# design.net
KiCad netlist of a schematic drawn in Altium Designer
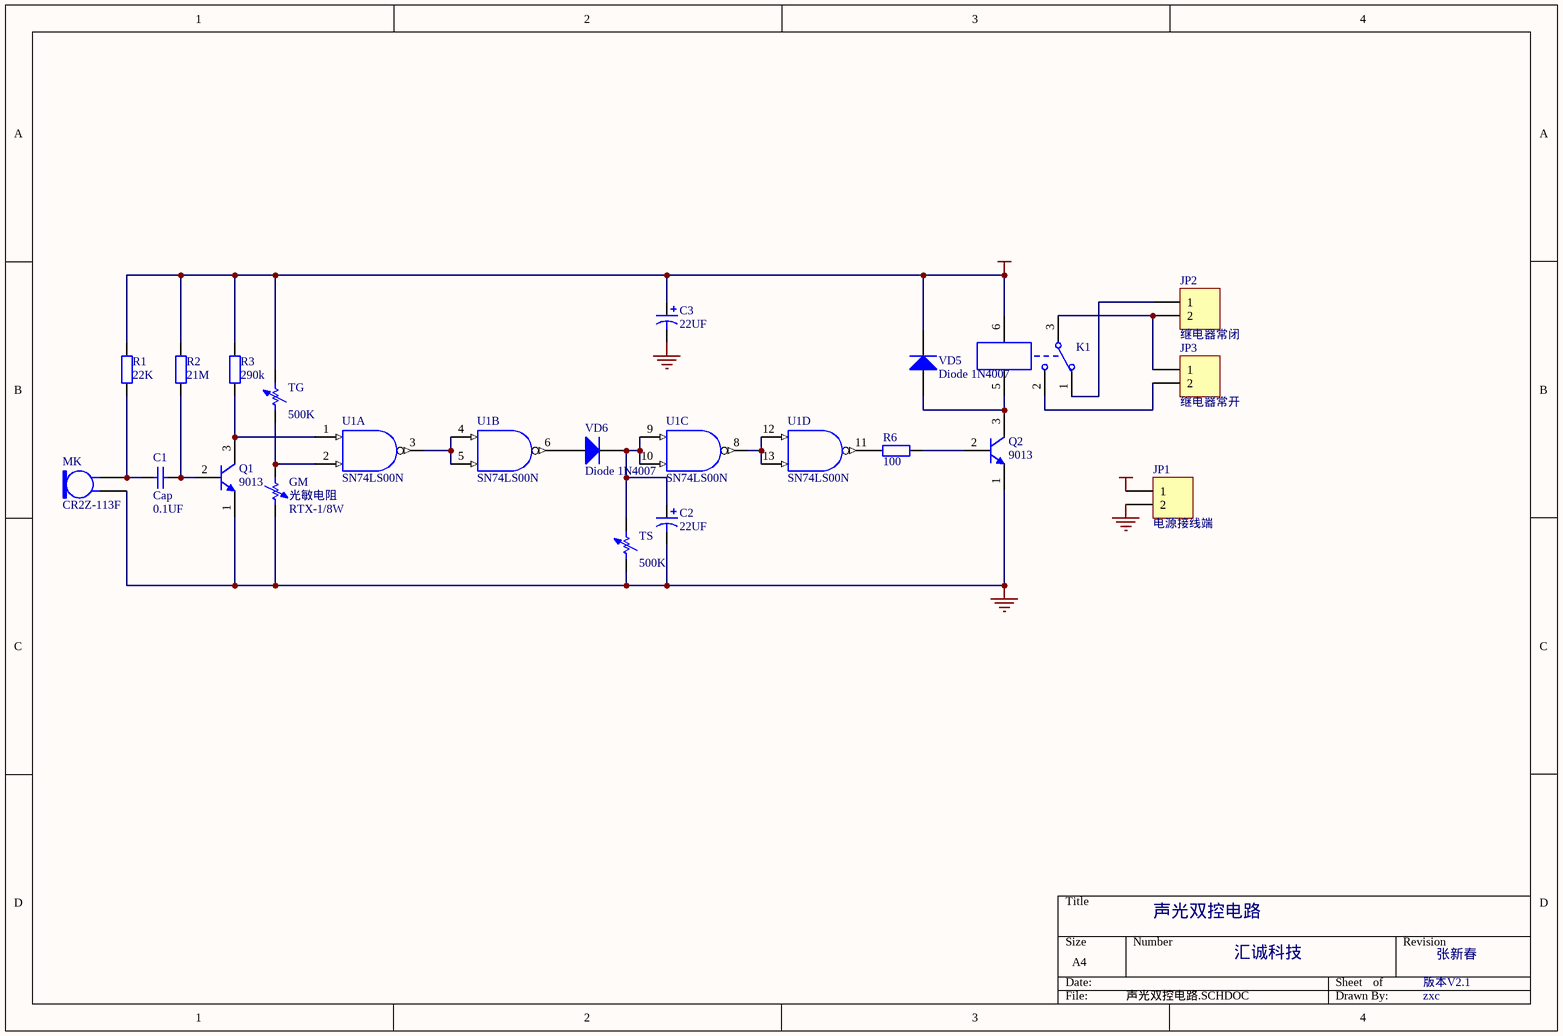
[diagram p0: 声光双控电路.SCHDOC]

(export (version "E")
  (design (tool "Eeschema 10.0.6"))
  (components
    (comp (ref "C1")
      (value "Cap")
      (footprint "HDR-2")
      (description "Capacitor")
      (fields (field (name "ALTIUM_VALUE") "0.1UF") (field (name "PUBLISHER") "Altium Limited"))
      (libsource (lib "Miscellaneous Devices") (part "Cap"))
    )
    (comp (ref "C2")
      (value "22UF")
      (footprint "C-DJ-4")
      (description "Polarized Capacitor (Radial)")
      (fields (field (name "PUBLISHER") "Altium Limited"))
      (libsource (lib "Miscellaneous Devices") (part "Cap Pol1"))
    )
    (comp (ref "C3")
      (value "22UF")
      (footprint "C-DJ-4")
      (description "Polarized Capacitor (Radial)")
      (fields (field (name "PUBLISHER") "Altium Limited"))
      (libsource (lib "Miscellaneous Devices") (part "Cap Pol1"))
    )
    (comp (ref "GM")
      (value "光敏电阻")
      (footprint "HDR-2")
      (description "Variable Resistor")
      (fields (field (name "ALTIUM_VALUE") "RTX-1/8W") (field (name "PUBLISHER") "Altium Limited"))
      (libsource (lib "Miscellaneous Devices") (part "Res Adj1"))
    )
    (comp (ref "JP1")
      (value "电源接线端")
      (footprint "JK128")
      (description "Header, 2-Pin, Right Angle")
      (fields (field (name "PUBLISHER") "Altium Limited"))
      (libsource (lib "Miscellaneous Connectors") (part "Header 2H"))
    )
    (comp (ref "JP2")
      (value "继电器常闭")
      (footprint "JK128")
      (description "Header, 2-Pin, Right Angle")
      (fields (field (name "PUBLISHER") "Altium Limited"))
      (libsource (lib "Miscellaneous Connectors") (part "Header 2H"))
    )
    (comp (ref "JP3")
      (value "继电器常开")
      (footprint "JK128")
      (description "Header, 2-Pin, Right Angle")
      (fields (field (name "PUBLISHER") "Altium Limited"))
      (libsource (lib "Miscellaneous Connectors") (part "Header 2H"))
    )
    (comp (ref "K1")
      (value "~")
      (footprint "JDQPF")
      (description "Single-Pole Dual-Throw Relay")
      (fields (field (name "PUBLISHER") "Altium Limited"))
      (libsource (lib "Miscellaneous Devices") (part "Relay-SPDT"))
    )
    (comp (ref "MK")
      (value "CR2Z-113F")
      (footprint "PIN2")
      (description "Microphone")
      (fields (field (name "PUBLISHER") "Altium Limited"))
      (libsource (lib "Miscellaneous Devices") (part "Mic2"))
    )
    (comp (ref "Q1")
      (value "9013")
      (footprint "BCY-W3")
      (description "NPN Bipolar Transistor")
      (fields (field (name "PUBLISHER") "Altium Limited"))
      (libsource (lib "Miscellaneous Devices") (part "NPN"))
    )
    (comp (ref "Q2")
      (value "9013")
      (footprint "BCY-W3")
      (description "NPN Bipolar Transistor")
      (fields (field (name "PUBLISHER") "Altium Limited"))
      (libsource (lib "Miscellaneous Devices") (part "NPN"))
    )
    (comp (ref "R1")
      (value "22K")
      (footprint "HDR-2")
      (description "Resistor")
      (fields (field (name "PUBLISHER") "Altium Limited"))
      (libsource (lib "") (part "Res2_1"))
    )
    (comp (ref "R2")
      (value "21M")
      (footprint "HDR-2")
      (description "Resistor")
      (fields (field (name "PUBLISHER") "Altium Limited"))
      (libsource (lib "") (part "Res2_1"))
    )
    (comp (ref "R3")
      (value "290k")
      (footprint "HDR-2")
      (description "Resistor")
      (fields (field (name "PUBLISHER") "Altium Limited"))
      (libsource (lib "") (part "Res2_1"))
    )
    (comp (ref "R6")
      (value "100")
      (footprint "HDR-2")
      (description "Resistor")
      (fields (field (name "PUBLISHER") "Altium Limited"))
      (libsource (lib "Miscellaneous Devices") (part "Res2"))
    )
    (comp (ref "TG")
      (value "500K")
      (footprint "HDR-3")
      (description "Variable Resistor")
      (fields (field (name "PUBLISHER") "Altium Limited"))
      (libsource (lib "Miscellaneous Devices") (part "Res Adj1"))
    )
    (comp (ref "TS")
      (value "500K")
      (footprint "HDR-3")
      (description "Variable Resistor")
      (fields (field (name "PUBLISHER") "Altium Limited"))
      (libsource (lib "Miscellaneous Devices") (part "Res Adj1"))
    )
    (comp (ref "U1")
      (value "SN74LS00N")
      (footprint "DIP-14/D19.7")
      (description "Quadruple 2-Input Positive-NAND Gate")
      (fields (field (name "MANUFACTURER") "Texas Instruments") (field (name "PUBLISHER") "Altium Limited"))
      (libsource (lib "TI Logic Gate 2") (part "SN74LS00N"))
    )
    (comp (ref "VD5")
      (value "Diode 1N4007")
      (footprint "DIO7.8-4.6x2")
      (description "1 Amp General Purpose Rectifier")
      (fields (field (name "PUBLISHER") "Altium Limited"))
      (libsource (lib "Miscellaneous Devices") (part "Diode 1N4007"))
    )
    (comp (ref "VD6")
      (value "Diode 1N4007")
      (footprint "DIO7.8-4.6x2")
      (description "1 Amp General Purpose Rectifier")
      (fields (field (name "PUBLISHER") "Altium Limited"))
      (libsource (lib "Miscellaneous Devices") (part "Diode 1N4007"))
    )
  )
  (nets
    (net (code "1") (name "GND") (class "Default")
      (node (ref "C2") (pin "2") (pinfunction "2_2") (pintype "passive"))
      (node (ref "C3") (pin "2") (pinfunction "2_2") (pintype "passive"))
      (node (ref "GM") (pin "2") (pinfunction "2_2") (pintype "passive"))
      (node (ref "JP1") (pin "2") (pinfunction "2_2") (pintype "passive"))
      (node (ref "MK") (pin "1") (pinfunction "1_1") (pintype "passive"))
      (node (ref "Q1") (pin "1") (pinfunction "E_1") (pintype "passive"))
      (node (ref "Q2") (pin "1") (pinfunction "E_1") (pintype "passive"))
      (node (ref "TS") (pin "1") (pinfunction "1_1") (pintype "passive"))
      (node (ref "U1") (pin "7") (pinfunction "GND_7") (pintype "power_in"))
    )
    (net (code "2") (name "Net-(C1-Pad1)") (class "Default")
      (node (ref "C1") (pin "1") (pinfunction "1_1") (pintype "passive"))
      (node (ref "MK") (pin "2") (pinfunction "2_2") (pintype "passive"))
      (node (ref "R1") (pin "1") (pinfunction "1_1") (pintype "passive"))
    )
    (net (code "3") (name "Net-(JP2-Pad1)") (class "Default")
      (node (ref "JP2") (pin "1") (pinfunction "1_1") (pintype "passive"))
      (node (ref "K1") (pin "1") (pinfunction "1_1") (pintype "passive"))
    )
    (net (code "4") (name "Net-(K1-2)") (class "Default")
      (node (ref "JP2") (pin "2") (pinfunction "2_2") (pintype "passive"))
      (node (ref "JP3") (pin "1") (pinfunction "1_1") (pintype "passive"))
      (node (ref "K1") (pin "3") (pinfunction "2_3") (pintype "passive"))
    )
    (net (code "5") (name "Net-(K1-3)") (class "Default")
      (node (ref "JP3") (pin "2") (pinfunction "2_2") (pintype "passive"))
      (node (ref "K1") (pin "2") (pinfunction "3_2") (pintype "passive"))
    )
    (net (code "6") (name "Net-(Q1-B)") (class "Default")
      (node (ref "C1") (pin "2") (pinfunction "2_2") (pintype "passive"))
      (node (ref "Q1") (pin "2") (pinfunction "B_2") (pintype "passive"))
      (node (ref "R2") (pin "1") (pinfunction "1_1") (pintype "passive"))
    )
    (net (code "7") (name "Net-(Q1-C)") (class "Default")
      (node (ref "Q1") (pin "3") (pinfunction "C_3") (pintype "passive"))
      (node (ref "R3") (pin "1") (pinfunction "1_1") (pintype "passive"))
      (node (ref "U1") (pin "1") (pinfunction "A_1") (pintype "input"))
    )
    (net (code "8") (name "Net-(Q2-B)") (class "Default")
      (node (ref "Q2") (pin "2") (pinfunction "B_2") (pintype "passive"))
      (node (ref "R6") (pin "2") (pinfunction "2_2") (pintype "passive"))
    )
    (net (code "9") (name "Net-(Q2-C)") (class "Default")
      (node (ref "K1") (pin "5") (pinfunction "5_5") (pintype "passive"))
      (node (ref "Q2") (pin "3") (pinfunction "C_3") (pintype "passive"))
      (node (ref "VD5") (pin "1") (pinfunction "A_1") (pintype "passive"))
    )
    (net (code "10") (name "Net-(U1A-B)") (class "Default")
      (node (ref "GM") (pin "1") (pinfunction "1_1") (pintype "passive"))
      (node (ref "TG") (pin "1") (pinfunction "1_1") (pintype "passive"))
      (node (ref "U1") (pin "2") (pinfunction "B_2") (pintype "input"))
    )
    (net (code "11") (name "Net-(U1A-Y)") (class "Default")
      (node (ref "U1") (pin "3") (pinfunction "Y_3") (pintype "output"))
      (node (ref "U1") (pin "4") (pinfunction "A_4") (pintype "input"))
      (node (ref "U1") (pin "5") (pinfunction "B_5") (pintype "input"))
    )
    (net (code "12") (name "Net-(U1B-Y)") (class "Default")
      (node (ref "U1") (pin "6") (pinfunction "Y_6") (pintype "output"))
      (node (ref "VD6") (pin "1") (pinfunction "A_1") (pintype "passive"))
    )
    (net (code "13") (name "Net-(U1C-A)") (class "Default")
      (node (ref "C2") (pin "1") (pinfunction "1_1") (pintype "passive"))
      (node (ref "TS") (pin "2") (pinfunction "2_2") (pintype "passive"))
      (node (ref "U1") (pin "10") (pinfunction "B_10") (pintype "input"))
      (node (ref "U1") (pin "9") (pinfunction "A_9") (pintype "input"))
      (node (ref "VD6") (pin "2") (pinfunction "K_2") (pintype "passive"))
    )
    (net (code "14") (name "Net-(U1C-Y)") (class "Default")
      (node (ref "U1") (pin "12") (pinfunction "A_12") (pintype "input"))
      (node (ref "U1") (pin "13") (pinfunction "B_13") (pintype "input"))
      (node (ref "U1") (pin "8") (pinfunction "Y_8") (pintype "output"))
    )
    (net (code "15") (name "Net-(U1D-Y)") (class "Default")
      (node (ref "R6") (pin "1") (pinfunction "1_1") (pintype "passive"))
      (node (ref "U1") (pin "11") (pinfunction "Y_11") (pintype "output"))
    )
    (net (code "16") (name "VCC") (class "Default")
      (node (ref "C3") (pin "1") (pinfunction "1_1") (pintype "passive"))
      (node (ref "JP1") (pin "1") (pinfunction "1_1") (pintype "passive"))
      (node (ref "K1") (pin "6") (pinfunction "6_6") (pintype "passive"))
      (node (ref "R1") (pin "2") (pinfunction "2_2") (pintype "passive"))
      (node (ref "R2") (pin "2") (pinfunction "2_2") (pintype "passive"))
      (node (ref "R3") (pin "2") (pinfunction "2_2") (pintype "passive"))
      (node (ref "TG") (pin "2") (pinfunction "2_2") (pintype "passive"))
      (node (ref "U1") (pin "14") (pinfunction "VCC_14") (pintype "power_in"))
      (node (ref "VD5") (pin "2") (pinfunction "K_2") (pintype "passive"))
    )
  )
)
